# LED_ROWS.net
KiCad netlist of a schematic drawn in Altium Designer
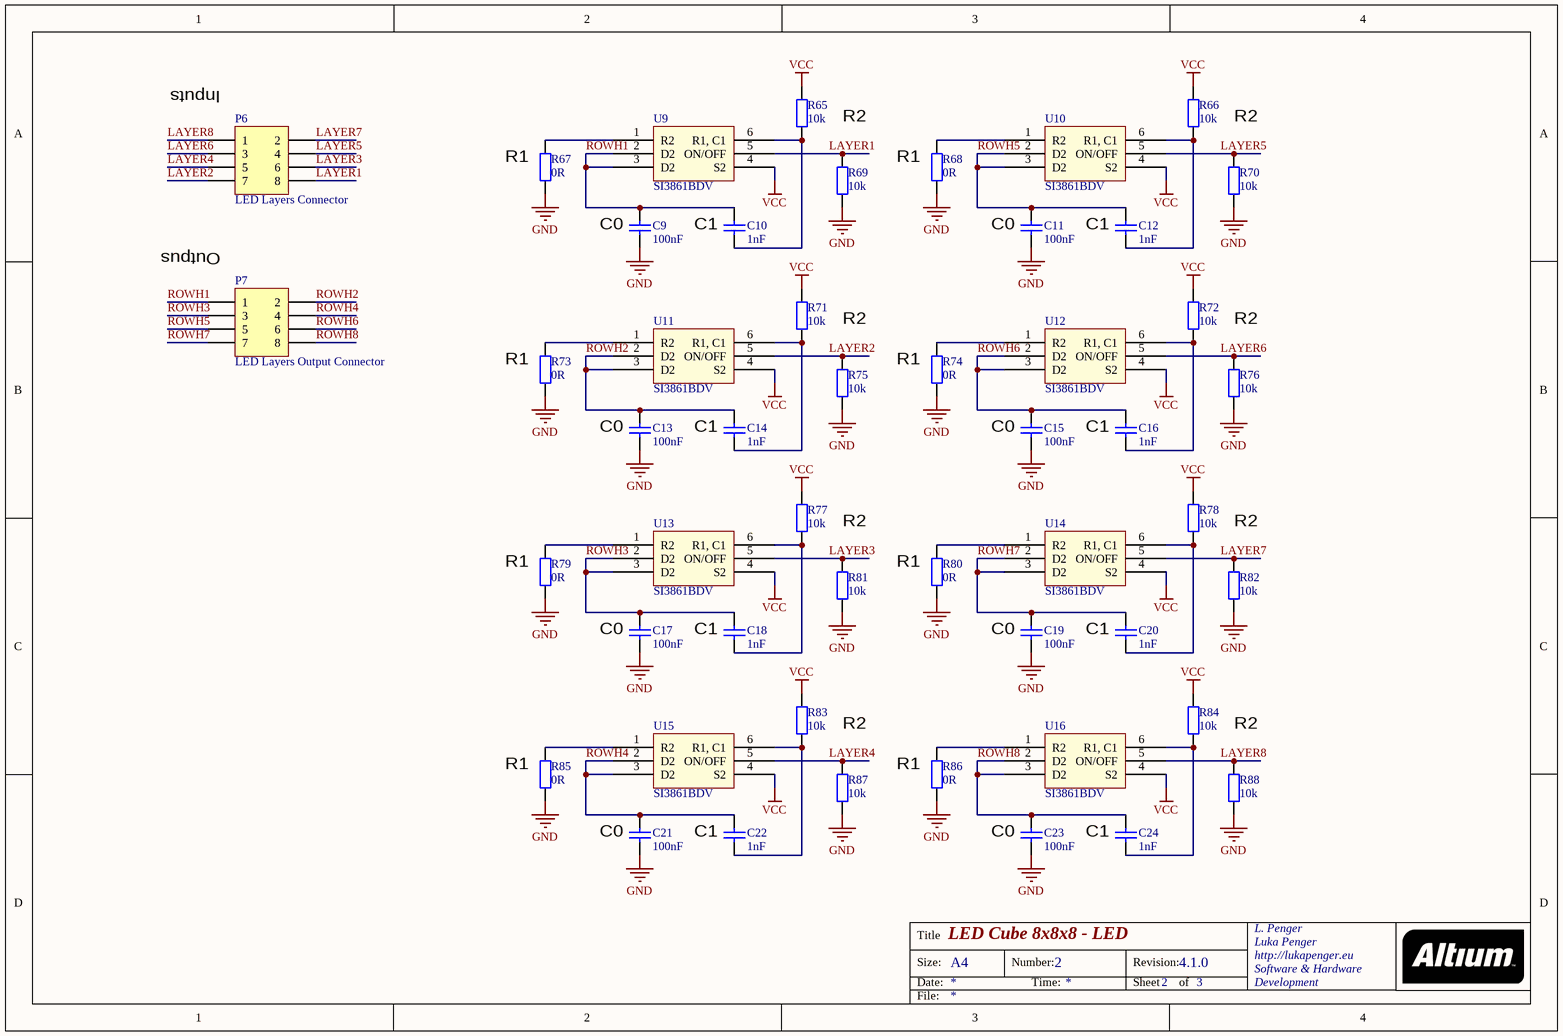
[diagram p0: LED_ROWS.SchDoc]

(export (version "E")
  (design (tool "Eeschema 10.0.6"))
  (components
    (comp (ref "C9")
      (value "100nF")
      (footprint "1608[0603]")
      (description "Capacitor")
      (fields (field (name "PUBLISHER") "Altium Limited"))
      (libsource (lib "Miscellaneous Devices") (part "Cap"))
    )
    (comp (ref "C10")
      (value "1nF")
      (footprint "1608[0603]")
      (description "Capacitor")
      (fields (field (name "PUBLISHER") "Altium Limited"))
      (libsource (lib "Miscellaneous Devices") (part "Cap"))
    )
    (comp (ref "C11")
      (value "100nF")
      (footprint "1608[0603]")
      (description "Capacitor")
      (fields (field (name "PUBLISHER") "Altium Limited"))
      (libsource (lib "Miscellaneous Devices") (part "Cap"))
    )
    (comp (ref "C12")
      (value "1nF")
      (footprint "1608[0603]")
      (description "Capacitor")
      (fields (field (name "PUBLISHER") "Altium Limited"))
      (libsource (lib "Miscellaneous Devices") (part "Cap"))
    )
    (comp (ref "C13")
      (value "100nF")
      (footprint "1608[0603]")
      (description "Capacitor")
      (fields (field (name "PUBLISHER") "Altium Limited"))
      (libsource (lib "Miscellaneous Devices") (part "Cap"))
    )
    (comp (ref "C14")
      (value "1nF")
      (footprint "1608[0603]")
      (description "Capacitor")
      (fields (field (name "PUBLISHER") "Altium Limited"))
      (libsource (lib "Miscellaneous Devices") (part "Cap"))
    )
    (comp (ref "C15")
      (value "100nF")
      (footprint "1608[0603]")
      (description "Capacitor")
      (fields (field (name "PUBLISHER") "Altium Limited"))
      (libsource (lib "Miscellaneous Devices") (part "Cap"))
    )
    (comp (ref "C16")
      (value "1nF")
      (footprint "1608[0603]")
      (description "Capacitor")
      (fields (field (name "PUBLISHER") "Altium Limited"))
      (libsource (lib "Miscellaneous Devices") (part "Cap"))
    )
    (comp (ref "C17")
      (value "100nF")
      (footprint "1608[0603]")
      (description "Capacitor")
      (fields (field (name "PUBLISHER") "Altium Limited"))
      (libsource (lib "Miscellaneous Devices") (part "Cap"))
    )
    (comp (ref "C18")
      (value "1nF")
      (footprint "1608[0603]")
      (description "Capacitor")
      (fields (field (name "PUBLISHER") "Altium Limited"))
      (libsource (lib "Miscellaneous Devices") (part "Cap"))
    )
    (comp (ref "C19")
      (value "100nF")
      (footprint "1608[0603]")
      (description "Capacitor")
      (fields (field (name "PUBLISHER") "Altium Limited"))
      (libsource (lib "Miscellaneous Devices") (part "Cap"))
    )
    (comp (ref "C20")
      (value "1nF")
      (footprint "1608[0603]")
      (description "Capacitor")
      (fields (field (name "PUBLISHER") "Altium Limited"))
      (libsource (lib "Miscellaneous Devices") (part "Cap"))
    )
    (comp (ref "C21")
      (value "100nF")
      (footprint "1608[0603]")
      (description "Capacitor")
      (fields (field (name "PUBLISHER") "Altium Limited"))
      (libsource (lib "Miscellaneous Devices") (part "Cap"))
    )
    (comp (ref "C22")
      (value "1nF")
      (footprint "1608[0603]")
      (description "Capacitor")
      (fields (field (name "PUBLISHER") "Altium Limited"))
      (libsource (lib "Miscellaneous Devices") (part "Cap"))
    )
    (comp (ref "C23")
      (value "100nF")
      (footprint "1608[0603]")
      (description "Capacitor")
      (fields (field (name "PUBLISHER") "Altium Limited"))
      (libsource (lib "Miscellaneous Devices") (part "Cap"))
    )
    (comp (ref "C24")
      (value "1nF")
      (footprint "1608[0603]")
      (description "Capacitor")
      (fields (field (name "PUBLISHER") "Altium Limited"))
      (libsource (lib "Miscellaneous Devices") (part "Cap"))
    )
    (comp (ref "P6")
      (value "LED Layers Connector")
      (footprint "IDC-2x4")
      (description "Header, 4-Pin, Dual row")
      (fields (field (name "PUBLISHER") "Altium Limited"))
      (libsource (lib "Miscellaneous Connectors") (part "Header 4X2"))
    )
    (comp (ref "P7")
      (value "LED Layers Output Connector")
      (footprint "IDC-2x4")
      (description "Header, 4-Pin, Dual row")
      (fields (field (name "PUBLISHER") "Altium Limited"))
      (libsource (lib "Miscellaneous Connectors") (part "Header 4X2"))
    )
    (comp (ref "R65")
      (value "10k")
      (footprint "1608[0603]")
      (description "Resistor")
      (fields (field (name "PUBLISHER") "Altium Limited"))
      (libsource (lib "Miscellaneous Devices") (part "Res2"))
    )
    (comp (ref "R66")
      (value "10k")
      (footprint "1608[0603]")
      (description "Resistor")
      (fields (field (name "PUBLISHER") "Altium Limited"))
      (libsource (lib "Miscellaneous Devices") (part "Res2"))
    )
    (comp (ref "R67")
      (value "0R")
      (footprint "1608[0603]")
      (description "Resistor")
      (fields (field (name "PUBLISHER") "Altium Limited"))
      (libsource (lib "") (part "Res2_1"))
    )
    (comp (ref "R68")
      (value "0R")
      (footprint "1608[0603]")
      (description "Resistor")
      (fields (field (name "PUBLISHER") "Altium Limited"))
      (libsource (lib "") (part "Res2_1"))
    )
    (comp (ref "R69")
      (value "10k")
      (footprint "1608[0603]")
      (description "Resistor")
      (fields (field (name "PUBLISHER") "Altium Limited"))
      (libsource (lib "Miscellaneous Devices") (part "Res2"))
    )
    (comp (ref "R70")
      (value "10k")
      (footprint "1608[0603]")
      (description "Resistor")
      (fields (field (name "PUBLISHER") "Altium Limited"))
      (libsource (lib "Miscellaneous Devices") (part "Res2"))
    )
    (comp (ref "R71")
      (value "10k")
      (footprint "1608[0603]")
      (description "Resistor")
      (fields (field (name "PUBLISHER") "Altium Limited"))
      (libsource (lib "Miscellaneous Devices") (part "Res2"))
    )
    (comp (ref "R72")
      (value "10k")
      (footprint "1608[0603]")
      (description "Resistor")
      (fields (field (name "PUBLISHER") "Altium Limited"))
      (libsource (lib "Miscellaneous Devices") (part "Res2"))
    )
    (comp (ref "R73")
      (value "0R")
      (footprint "1608[0603]")
      (description "Resistor")
      (fields (field (name "PUBLISHER") "Altium Limited"))
      (libsource (lib "") (part "Res2_1"))
    )
    (comp (ref "R74")
      (value "0R")
      (footprint "1608[0603]")
      (description "Resistor")
      (fields (field (name "PUBLISHER") "Altium Limited"))
      (libsource (lib "") (part "Res2_1"))
    )
    (comp (ref "R75")
      (value "10k")
      (footprint "1608[0603]")
      (description "Resistor")
      (fields (field (name "PUBLISHER") "Altium Limited"))
      (libsource (lib "Miscellaneous Devices") (part "Res2"))
    )
    (comp (ref "R76")
      (value "10k")
      (footprint "1608[0603]")
      (description "Resistor")
      (fields (field (name "PUBLISHER") "Altium Limited"))
      (libsource (lib "Miscellaneous Devices") (part "Res2"))
    )
    (comp (ref "R77")
      (value "10k")
      (footprint "1608[0603]")
      (description "Resistor")
      (fields (field (name "PUBLISHER") "Altium Limited"))
      (libsource (lib "Miscellaneous Devices") (part "Res2"))
    )
    (comp (ref "R78")
      (value "10k")
      (footprint "1608[0603]")
      (description "Resistor")
      (fields (field (name "PUBLISHER") "Altium Limited"))
      (libsource (lib "Miscellaneous Devices") (part "Res2"))
    )
    (comp (ref "R79")
      (value "0R")
      (footprint "1608[0603]")
      (description "Resistor")
      (fields (field (name "PUBLISHER") "Altium Limited"))
      (libsource (lib "") (part "Res2_1"))
    )
    (comp (ref "R80")
      (value "0R")
      (footprint "1608[0603]")
      (description "Resistor")
      (fields (field (name "PUBLISHER") "Altium Limited"))
      (libsource (lib "") (part "Res2_1"))
    )
    (comp (ref "R81")
      (value "10k")
      (footprint "1608[0603]")
      (description "Resistor")
      (fields (field (name "PUBLISHER") "Altium Limited"))
      (libsource (lib "Miscellaneous Devices") (part "Res2"))
    )
    (comp (ref "R82")
      (value "10k")
      (footprint "1608[0603]")
      (description "Resistor")
      (fields (field (name "PUBLISHER") "Altium Limited"))
      (libsource (lib "Miscellaneous Devices") (part "Res2"))
    )
    (comp (ref "R83")
      (value "10k")
      (footprint "1608[0603]")
      (description "Resistor")
      (fields (field (name "PUBLISHER") "Altium Limited"))
      (libsource (lib "Miscellaneous Devices") (part "Res2"))
    )
    (comp (ref "R84")
      (value "10k")
      (footprint "1608[0603]")
      (description "Resistor")
      (fields (field (name "PUBLISHER") "Altium Limited"))
      (libsource (lib "Miscellaneous Devices") (part "Res2"))
    )
    (comp (ref "R85")
      (value "0R")
      (footprint "1608[0603]")
      (description "Resistor")
      (fields (field (name "PUBLISHER") "Altium Limited"))
      (libsource (lib "") (part "Res2_1"))
    )
    (comp (ref "R86")
      (value "0R")
      (footprint "1608[0603]")
      (description "Resistor")
      (fields (field (name "PUBLISHER") "Altium Limited"))
      (libsource (lib "") (part "Res2_1"))
    )
    (comp (ref "R87")
      (value "10k")
      (footprint "1608[0603]")
      (description "Resistor")
      (fields (field (name "PUBLISHER") "Altium Limited"))
      (libsource (lib "Miscellaneous Devices") (part "Res2"))
    )
    (comp (ref "R88")
      (value "10k")
      (footprint "1608[0603]")
      (description "Resistor")
      (fields (field (name "PUBLISHER") "Altium Limited"))
      (libsource (lib "Miscellaneous Devices") (part "Res2"))
    )
    (comp (ref "U9")
      (value "SI3861BDV")
      (footprint "TSOP 6")
      (description "4.5 - 20V 2.3A Load Switch")
      (libsource (lib "LukaLIBRARY") (part "SI3861BDV"))
    )
    (comp (ref "U10")
      (value "SI3861BDV")
      (footprint "TSOP 6")
      (description "4.5 - 20V 2.3A Load Switch")
      (libsource (lib "LukaLIBRARY") (part "SI3861BDV"))
    )
    (comp (ref "U11")
      (value "SI3861BDV")
      (footprint "TSOP 6")
      (description "4.5 - 20V 2.3A Load Switch")
      (libsource (lib "LukaLIBRARY") (part "SI3861BDV"))
    )
    (comp (ref "U12")
      (value "SI3861BDV")
      (footprint "TSOP 6")
      (description "4.5 - 20V 2.3A Load Switch")
      (libsource (lib "LukaLIBRARY") (part "SI3861BDV"))
    )
    (comp (ref "U13")
      (value "SI3861BDV")
      (footprint "TSOP 6")
      (description "4.5 - 20V 2.3A Load Switch")
      (libsource (lib "LukaLIBRARY") (part "SI3861BDV"))
    )
    (comp (ref "U14")
      (value "SI3861BDV")
      (footprint "TSOP 6")
      (description "4.5 - 20V 2.3A Load Switch")
      (libsource (lib "LukaLIBRARY") (part "SI3861BDV"))
    )
    (comp (ref "U15")
      (value "SI3861BDV")
      (footprint "TSOP 6")
      (description "4.5 - 20V 2.3A Load Switch")
      (libsource (lib "LukaLIBRARY") (part "SI3861BDV"))
    )
    (comp (ref "U16")
      (value "SI3861BDV")
      (footprint "TSOP 6")
      (description "4.5 - 20V 2.3A Load Switch")
      (libsource (lib "LukaLIBRARY") (part "SI3861BDV"))
    )
  )
  (nets
    (net (code "1") (name "/LAYER1") (class "Default")
      (node (ref "P6") (pin "8") (pinfunction "8_8") (pintype "passive"))
      (node (ref "R69") (pin "2") (pinfunction "2_2") (pintype "passive"))
      (node (ref "U9") (pin "5") (pinfunction "ON/OFF_5") (pintype "passive"))
    )
    (net (code "2") (name "/LAYER2") (class "Default")
      (node (ref "P6") (pin "7") (pinfunction "7_7") (pintype "passive"))
      (node (ref "R75") (pin "2") (pinfunction "2_2") (pintype "passive"))
      (node (ref "U11") (pin "5") (pinfunction "ON/OFF_5") (pintype "passive"))
    )
    (net (code "3") (name "/LAYER3") (class "Default")
      (node (ref "P6") (pin "6") (pinfunction "6_6") (pintype "passive"))
      (node (ref "R81") (pin "2") (pinfunction "2_2") (pintype "passive"))
      (node (ref "U13") (pin "5") (pinfunction "ON/OFF_5") (pintype "passive"))
    )
    (net (code "4") (name "/LAYER4") (class "Default")
      (node (ref "P6") (pin "5") (pinfunction "5_5") (pintype "passive"))
      (node (ref "R87") (pin "2") (pinfunction "2_2") (pintype "passive"))
      (node (ref "U15") (pin "5") (pinfunction "ON/OFF_5") (pintype "passive"))
    )
    (net (code "5") (name "/LAYER5") (class "Default")
      (node (ref "P6") (pin "4") (pinfunction "4_4") (pintype "passive"))
      (node (ref "R70") (pin "2") (pinfunction "2_2") (pintype "passive"))
      (node (ref "U10") (pin "5") (pinfunction "ON/OFF_5") (pintype "passive"))
    )
    (net (code "6") (name "/LAYER6") (class "Default")
      (node (ref "P6") (pin "3") (pinfunction "3_3") (pintype "passive"))
      (node (ref "R76") (pin "2") (pinfunction "2_2") (pintype "passive"))
      (node (ref "U12") (pin "5") (pinfunction "ON/OFF_5") (pintype "passive"))
    )
    (net (code "7") (name "/LAYER7") (class "Default")
      (node (ref "P6") (pin "2") (pinfunction "2_2") (pintype "passive"))
      (node (ref "R82") (pin "2") (pinfunction "2_2") (pintype "passive"))
      (node (ref "U14") (pin "5") (pinfunction "ON/OFF_5") (pintype "passive"))
    )
    (net (code "8") (name "/LAYER8") (class "Default")
      (node (ref "P6") (pin "1") (pinfunction "1_1") (pintype "passive"))
      (node (ref "R88") (pin "2") (pinfunction "2_2") (pintype "passive"))
      (node (ref "U16") (pin "5") (pinfunction "ON/OFF_5") (pintype "passive"))
    )
    (net (code "9") (name "/ROWH1") (class "Default")
      (node (ref "C10") (pin "1") (pinfunction "1_1") (pintype "passive"))
      (node (ref "C9") (pin "1") (pinfunction "1_1") (pintype "passive"))
      (node (ref "P7") (pin "1") (pinfunction "1_1") (pintype "passive"))
      (node (ref "U9") (pin "2") (pinfunction "D2_2") (pintype "passive"))
      (node (ref "U9") (pin "3") (pinfunction "D2_3") (pintype "passive"))
    )
    (net (code "10") (name "/ROWH2") (class "Default")
      (node (ref "C13") (pin "1") (pinfunction "1_1") (pintype "passive"))
      (node (ref "C14") (pin "1") (pinfunction "1_1") (pintype "passive"))
      (node (ref "P7") (pin "2") (pinfunction "2_2") (pintype "passive"))
      (node (ref "U11") (pin "2") (pinfunction "D2_2") (pintype "passive"))
      (node (ref "U11") (pin "3") (pinfunction "D2_3") (pintype "passive"))
    )
    (net (code "11") (name "/ROWH3") (class "Default")
      (node (ref "C17") (pin "1") (pinfunction "1_1") (pintype "passive"))
      (node (ref "C18") (pin "1") (pinfunction "1_1") (pintype "passive"))
      (node (ref "P7") (pin "3") (pinfunction "3_3") (pintype "passive"))
      (node (ref "U13") (pin "2") (pinfunction "D2_2") (pintype "passive"))
      (node (ref "U13") (pin "3") (pinfunction "D2_3") (pintype "passive"))
    )
    (net (code "12") (name "/ROWH4") (class "Default")
      (node (ref "C21") (pin "1") (pinfunction "1_1") (pintype "passive"))
      (node (ref "C22") (pin "1") (pinfunction "1_1") (pintype "passive"))
      (node (ref "P7") (pin "4") (pinfunction "4_4") (pintype "passive"))
      (node (ref "U15") (pin "2") (pinfunction "D2_2") (pintype "passive"))
      (node (ref "U15") (pin "3") (pinfunction "D2_3") (pintype "passive"))
    )
    (net (code "13") (name "/ROWH5") (class "Default")
      (node (ref "C11") (pin "1") (pinfunction "1_1") (pintype "passive"))
      (node (ref "C12") (pin "1") (pinfunction "1_1") (pintype "passive"))
      (node (ref "P7") (pin "5") (pinfunction "5_5") (pintype "passive"))
      (node (ref "U10") (pin "2") (pinfunction "D2_2") (pintype "passive"))
      (node (ref "U10") (pin "3") (pinfunction "D2_3") (pintype "passive"))
    )
    (net (code "14") (name "/ROWH6") (class "Default")
      (node (ref "C15") (pin "1") (pinfunction "1_1") (pintype "passive"))
      (node (ref "C16") (pin "1") (pinfunction "1_1") (pintype "passive"))
      (node (ref "P7") (pin "6") (pinfunction "6_6") (pintype "passive"))
      (node (ref "U12") (pin "2") (pinfunction "D2_2") (pintype "passive"))
      (node (ref "U12") (pin "3") (pinfunction "D2_3") (pintype "passive"))
    )
    (net (code "15") (name "/ROWH7") (class "Default")
      (node (ref "C19") (pin "1") (pinfunction "1_1") (pintype "passive"))
      (node (ref "C20") (pin "1") (pinfunction "1_1") (pintype "passive"))
      (node (ref "P7") (pin "7") (pinfunction "7_7") (pintype "passive"))
      (node (ref "U14") (pin "2") (pinfunction "D2_2") (pintype "passive"))
      (node (ref "U14") (pin "3") (pinfunction "D2_3") (pintype "passive"))
    )
    (net (code "16") (name "/ROWH8") (class "Default")
      (node (ref "C23") (pin "1") (pinfunction "1_1") (pintype "passive"))
      (node (ref "C24") (pin "1") (pinfunction "1_1") (pintype "passive"))
      (node (ref "P7") (pin "8") (pinfunction "8_8") (pintype "passive"))
      (node (ref "U16") (pin "2") (pinfunction "D2_2") (pintype "passive"))
      (node (ref "U16") (pin "3") (pinfunction "D2_3") (pintype "passive"))
    )
    (net (code "17") (name "GND") (class "Default")
      (node (ref "C11") (pin "2") (pinfunction "2_2") (pintype "passive"))
      (node (ref "C13") (pin "2") (pinfunction "2_2") (pintype "passive"))
      (node (ref "C15") (pin "2") (pinfunction "2_2") (pintype "passive"))
      (node (ref "C17") (pin "2") (pinfunction "2_2") (pintype "passive"))
      (node (ref "C19") (pin "2") (pinfunction "2_2") (pintype "passive"))
      (node (ref "C21") (pin "2") (pinfunction "2_2") (pintype "passive"))
      (node (ref "C23") (pin "2") (pinfunction "2_2") (pintype "passive"))
      (node (ref "C9") (pin "2") (pinfunction "2_2") (pintype "passive"))
      (node (ref "R67") (pin "2") (pinfunction "2_2") (pintype "passive"))
      (node (ref "R68") (pin "2") (pinfunction "2_2") (pintype "passive"))
      (node (ref "R69") (pin "1") (pinfunction "1_1") (pintype "passive"))
      (node (ref "R70") (pin "1") (pinfunction "1_1") (pintype "passive"))
      (node (ref "R73") (pin "2") (pinfunction "2_2") (pintype "passive"))
      (node (ref "R74") (pin "2") (pinfunction "2_2") (pintype "passive"))
      (node (ref "R75") (pin "1") (pinfunction "1_1") (pintype "passive"))
      (node (ref "R76") (pin "1") (pinfunction "1_1") (pintype "passive"))
      (node (ref "R79") (pin "2") (pinfunction "2_2") (pintype "passive"))
      (node (ref "R80") (pin "2") (pinfunction "2_2") (pintype "passive"))
      (node (ref "R81") (pin "1") (pinfunction "1_1") (pintype "passive"))
      (node (ref "R82") (pin "1") (pinfunction "1_1") (pintype "passive"))
      (node (ref "R85") (pin "2") (pinfunction "2_2") (pintype "passive"))
      (node (ref "R86") (pin "2") (pinfunction "2_2") (pintype "passive"))
      (node (ref "R87") (pin "1") (pinfunction "1_1") (pintype "passive"))
      (node (ref "R88") (pin "1") (pinfunction "1_1") (pintype "passive"))
    )
    (net (code "18") (name "Net-(U9-R1,_C1)") (class "Default")
      (node (ref "C10") (pin "2") (pinfunction "2_2") (pintype "passive"))
      (node (ref "R65") (pin "1") (pinfunction "1_1") (pintype "passive"))
      (node (ref "U9") (pin "6") (pinfunction "R1,_C1_6") (pintype "passive"))
    )
    (net (code "19") (name "Net-(U9-R2)") (class "Default")
      (node (ref "R67") (pin "1") (pinfunction "1_1") (pintype "passive"))
      (node (ref "U9") (pin "1") (pinfunction "R2_1") (pintype "passive"))
    )
    (net (code "20") (name "Net-(U10-R1,_C1)") (class "Default")
      (node (ref "C12") (pin "2") (pinfunction "2_2") (pintype "passive"))
      (node (ref "R66") (pin "1") (pinfunction "1_1") (pintype "passive"))
      (node (ref "U10") (pin "6") (pinfunction "R1,_C1_6") (pintype "passive"))
    )
    (net (code "21") (name "Net-(U10-R2)") (class "Default")
      (node (ref "R68") (pin "1") (pinfunction "1_1") (pintype "passive"))
      (node (ref "U10") (pin "1") (pinfunction "R2_1") (pintype "passive"))
    )
    (net (code "22") (name "Net-(U11-R1,_C1)") (class "Default")
      (node (ref "C14") (pin "2") (pinfunction "2_2") (pintype "passive"))
      (node (ref "R71") (pin "1") (pinfunction "1_1") (pintype "passive"))
      (node (ref "U11") (pin "6") (pinfunction "R1,_C1_6") (pintype "passive"))
    )
    (net (code "23") (name "Net-(U11-R2)") (class "Default")
      (node (ref "R73") (pin "1") (pinfunction "1_1") (pintype "passive"))
      (node (ref "U11") (pin "1") (pinfunction "R2_1") (pintype "passive"))
    )
    (net (code "24") (name "Net-(U12-R1,_C1)") (class "Default")
      (node (ref "C16") (pin "2") (pinfunction "2_2") (pintype "passive"))
      (node (ref "R72") (pin "1") (pinfunction "1_1") (pintype "passive"))
      (node (ref "U12") (pin "6") (pinfunction "R1,_C1_6") (pintype "passive"))
    )
    (net (code "25") (name "Net-(U12-R2)") (class "Default")
      (node (ref "R74") (pin "1") (pinfunction "1_1") (pintype "passive"))
      (node (ref "U12") (pin "1") (pinfunction "R2_1") (pintype "passive"))
    )
    (net (code "26") (name "Net-(U13-R1,_C1)") (class "Default")
      (node (ref "C18") (pin "2") (pinfunction "2_2") (pintype "passive"))
      (node (ref "R77") (pin "1") (pinfunction "1_1") (pintype "passive"))
      (node (ref "U13") (pin "6") (pinfunction "R1,_C1_6") (pintype "passive"))
    )
    (net (code "27") (name "Net-(U13-R2)") (class "Default")
      (node (ref "R79") (pin "1") (pinfunction "1_1") (pintype "passive"))
      (node (ref "U13") (pin "1") (pinfunction "R2_1") (pintype "passive"))
    )
    (net (code "28") (name "Net-(U14-R1,_C1)") (class "Default")
      (node (ref "C20") (pin "2") (pinfunction "2_2") (pintype "passive"))
      (node (ref "R78") (pin "1") (pinfunction "1_1") (pintype "passive"))
      (node (ref "U14") (pin "6") (pinfunction "R1,_C1_6") (pintype "passive"))
    )
    (net (code "29") (name "Net-(U14-R2)") (class "Default")
      (node (ref "R80") (pin "1") (pinfunction "1_1") (pintype "passive"))
      (node (ref "U14") (pin "1") (pinfunction "R2_1") (pintype "passive"))
    )
    (net (code "30") (name "Net-(U15-R1,_C1)") (class "Default")
      (node (ref "C22") (pin "2") (pinfunction "2_2") (pintype "passive"))
      (node (ref "R83") (pin "1") (pinfunction "1_1") (pintype "passive"))
      (node (ref "U15") (pin "6") (pinfunction "R1,_C1_6") (pintype "passive"))
    )
    (net (code "31") (name "Net-(U15-R2)") (class "Default")
      (node (ref "R85") (pin "1") (pinfunction "1_1") (pintype "passive"))
      (node (ref "U15") (pin "1") (pinfunction "R2_1") (pintype "passive"))
    )
    (net (code "32") (name "Net-(U16-R1,_C1)") (class "Default")
      (node (ref "C24") (pin "2") (pinfunction "2_2") (pintype "passive"))
      (node (ref "R84") (pin "1") (pinfunction "1_1") (pintype "passive"))
      (node (ref "U16") (pin "6") (pinfunction "R1,_C1_6") (pintype "passive"))
    )
    (net (code "33") (name "Net-(U16-R2)") (class "Default")
      (node (ref "R86") (pin "1") (pinfunction "1_1") (pintype "passive"))
      (node (ref "U16") (pin "1") (pinfunction "R2_1") (pintype "passive"))
    )
    (net (code "34") (name "VCC") (class "Default")
      (node (ref "R65") (pin "2") (pinfunction "2_2") (pintype "passive"))
      (node (ref "R66") (pin "2") (pinfunction "2_2") (pintype "passive"))
      (node (ref "R71") (pin "2") (pinfunction "2_2") (pintype "passive"))
      (node (ref "R72") (pin "2") (pinfunction "2_2") (pintype "passive"))
      (node (ref "R77") (pin "2") (pinfunction "2_2") (pintype "passive"))
      (node (ref "R78") (pin "2") (pinfunction "2_2") (pintype "passive"))
      (node (ref "R83") (pin "2") (pinfunction "2_2") (pintype "passive"))
      (node (ref "R84") (pin "2") (pinfunction "2_2") (pintype "passive"))
      (node (ref "U10") (pin "4") (pinfunction "S2_4") (pintype "passive"))
      (node (ref "U11") (pin "4") (pinfunction "S2_4") (pintype "passive"))
      (node (ref "U12") (pin "4") (pinfunction "S2_4") (pintype "passive"))
      (node (ref "U13") (pin "4") (pinfunction "S2_4") (pintype "passive"))
      (node (ref "U14") (pin "4") (pinfunction "S2_4") (pintype "passive"))
      (node (ref "U15") (pin "4") (pinfunction "S2_4") (pintype "passive"))
      (node (ref "U16") (pin "4") (pinfunction "S2_4") (pintype "passive"))
      (node (ref "U9") (pin "4") (pinfunction "S2_4") (pintype "passive"))
    )
  )
)
